# RPiCanInterface.net
KiCad netlist of a schematic drawn in EAGLE
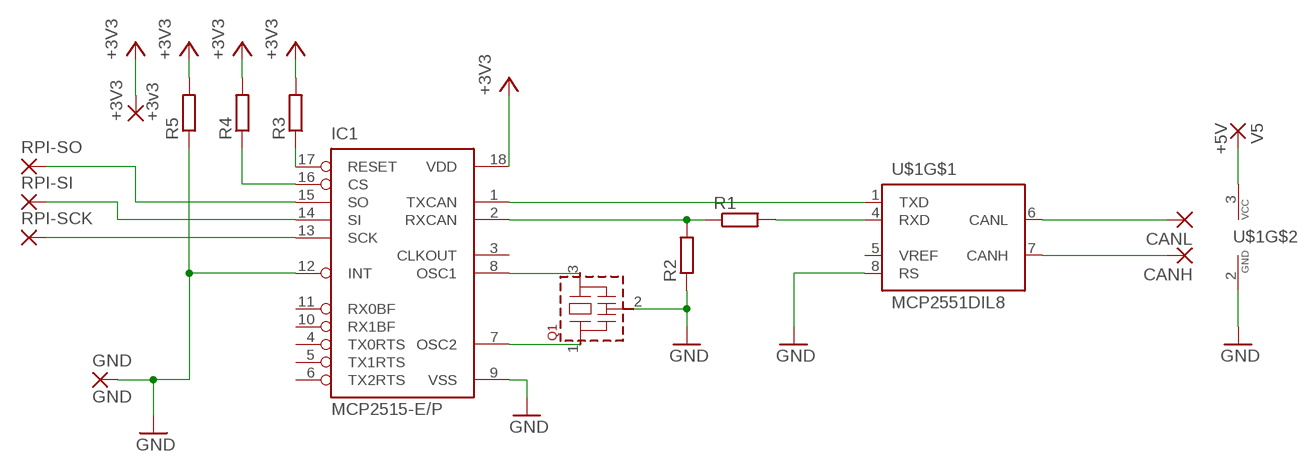
[diagram p0: schematic, sheet 1]

(export (version "E")
  (design (tool "Eeschema 10.0.6"))
  (components
    (comp (ref "+3V3")
      (value "+3v3")
      (footprint "eagle-import:1,6_0,8")
      (libsource (lib "eagle-import") (part "1,6/0,8"))
    )
    (comp (ref "CANH")
      (value "1,6/0,8")
      (footprint "eagle-import:1,6_0,8")
      (libsource (lib "eagle-import") (part "1,6/0,8"))
    )
    (comp (ref "CANL")
      (value "1,6/0,8")
      (footprint "eagle-import:1,6_0,8")
      (libsource (lib "eagle-import") (part "1,6/0,8"))
    )
    (comp (ref "GND")
      (value "GND")
      (footprint "eagle-import:1,6_0,8")
      (libsource (lib "eagle-import") (part "1,6/0,8"))
    )
    (comp (ref "IC1")
      (value "MCP2515-E/P")
      (footprint "eagle-import:DIL18")
      (libsource (lib "eagle-import") (part "MCP2515-E/P"))
    )
    (comp (ref "Q1")
      (value "CSTLA_T")
      (footprint "eagle-import:CSTLA_T")
      (libsource (lib "eagle-import") (part "CSTLA_T"))
    )
    (comp (ref "R1")
      (value "R-EU_0207/7")
      (footprint "eagle-import:0207_7")
      (libsource (lib "eagle-import") (part "R-EU_0207/7"))
    )
    (comp (ref "R2")
      (value "R-EU_0207/7")
      (footprint "eagle-import:0207_7")
      (libsource (lib "eagle-import") (part "R-EU_0207/7"))
    )
    (comp (ref "R3")
      (value "R-EU_0207/7")
      (footprint "eagle-import:0207_7")
      (libsource (lib "eagle-import") (part "R-EU_0207/7"))
    )
    (comp (ref "R4")
      (value "R-EU_0207/7")
      (footprint "eagle-import:0207_7")
      (libsource (lib "eagle-import") (part "R-EU_0207/7"))
    )
    (comp (ref "R5")
      (value "R-EU_0207/7")
      (footprint "eagle-import:0207_7")
      (libsource (lib "eagle-import") (part "R-EU_0207/7"))
    )
    (comp (ref "RPI-SCK")
      (value "1,6/0,8")
      (footprint "eagle-import:1,6_0,8")
      (libsource (lib "eagle-import") (part "1,6/0,8"))
    )
    (comp (ref "RPI-SI")
      (value "1,6/0,8")
      (footprint "eagle-import:1,6_0,8")
      (libsource (lib "eagle-import") (part "1,6/0,8"))
    )
    (comp (ref "RPI-SO")
      (value "1,6/0,8")
      (footprint "eagle-import:1,6_0,8")
      (libsource (lib "eagle-import") (part "1,6/0,8"))
    )
    (comp (ref "U$1")
      (value "MCP2551DIL8")
      (footprint "eagle-import:DIL08")
      (libsource (lib "eagle-import") (part "MCP2551DIL8"))
    )
    (comp (ref "V5")
      (value "+5V")
      (footprint "eagle-import:1,6_0,8")
      (libsource (lib "eagle-import") (part "1,6/0,8"))
    )
  )
  (nets
    (net (code "1") (name "+3V3") (class "Default")
      (node (ref "+3V3") (pin "1") (pinfunction "P_1") (pintype "passive"))
      (node (ref "IC1") (pin "18") (pinfunction "VDD_18") (pintype "power_in"))
      (node (ref "R3") (pin "2") (pinfunction "2_2") (pintype "passive"))
      (node (ref "R4") (pin "2") (pinfunction "2_2") (pintype "passive"))
      (node (ref "R5") (pin "2") (pinfunction "2_2") (pintype "passive"))
    )
    (net (code "2") (name "GND") (class "Default")
      (node (ref "GND") (pin "1") (pinfunction "P_1") (pintype "passive"))
      (node (ref "IC1") (pin "12") (pinfunction "INT_12") (pintype "output"))
      (node (ref "IC1") (pin "9") (pinfunction "VSS_9") (pintype "power_in"))
      (node (ref "Q1") (pin "2") (pinfunction "VSS_2") (pintype "power_in"))
      (node (ref "R2") (pin "1") (pinfunction "1_1") (pintype "passive"))
      (node (ref "R5") (pin "1") (pinfunction "1_1") (pintype "passive"))
      (node (ref "U$1") (pin "2") (pinfunction "GND_2") (pintype "power_in"))
      (node (ref "U$1") (pin "8") (pinfunction "RS_8") (pintype "bidirectional"))
    )
    (net (code "3") (name "Net-(CANH-P)") (class "Default")
      (node (ref "CANH") (pin "1") (pinfunction "P_1") (pintype "passive"))
      (node (ref "U$1") (pin "7") (pinfunction "CANH_7") (pintype "bidirectional"))
    )
    (net (code "4") (name "Net-(CANL-P)") (class "Default")
      (node (ref "CANL") (pin "1") (pinfunction "P_1") (pintype "passive"))
      (node (ref "U$1") (pin "6") (pinfunction "CANL_6") (pintype "bidirectional"))
    )
    (net (code "5") (name "Net-(IC1-CS)") (class "Default")
      (node (ref "IC1") (pin "16") (pinfunction "CS_16") (pintype "input"))
      (node (ref "R4") (pin "1") (pinfunction "1_1") (pintype "passive"))
    )
    (net (code "6") (name "Net-(IC1-OSC1)") (class "Default")
      (node (ref "IC1") (pin "8") (pinfunction "OSC1_8") (pintype "input"))
      (node (ref "Q1") (pin "3") (pinfunction "3_3") (pintype "input"))
    )
    (net (code "7") (name "Net-(IC1-OSC2)") (class "Default")
      (node (ref "IC1") (pin "7") (pinfunction "OSC2_7") (pintype "output"))
      (node (ref "Q1") (pin "1") (pinfunction "1_1") (pintype "output"))
    )
    (net (code "8") (name "Net-(IC1-RESET)") (class "Default")
      (node (ref "IC1") (pin "17") (pinfunction "RESET_17") (pintype "input"))
      (node (ref "R3") (pin "1") (pinfunction "1_1") (pintype "passive"))
    )
    (net (code "9") (name "Net-(IC1-RXCAN)") (class "Default")
      (node (ref "IC1") (pin "2") (pinfunction "RXCAN_2") (pintype "input"))
      (node (ref "R1") (pin "1") (pinfunction "1_1") (pintype "passive"))
      (node (ref "R2") (pin "2") (pinfunction "2_2") (pintype "passive"))
    )
    (net (code "10") (name "Net-(IC1-SCK)") (class "Default")
      (node (ref "IC1") (pin "13") (pinfunction "SCK_13") (pintype "input"))
      (node (ref "RPI-SCK") (pin "1") (pinfunction "P_1") (pintype "passive"))
    )
    (net (code "11") (name "Net-(IC1-SI)") (class "Default")
      (node (ref "IC1") (pin "14") (pinfunction "SI_14") (pintype "input"))
      (node (ref "RPI-SI") (pin "1") (pinfunction "P_1") (pintype "passive"))
    )
    (net (code "12") (name "Net-(IC1-SO)") (class "Default")
      (node (ref "IC1") (pin "15") (pinfunction "SO_15") (pintype "output"))
      (node (ref "RPI-SO") (pin "1") (pinfunction "P_1") (pintype "passive"))
    )
    (net (code "13") (name "Net-(IC1-TXCAN)") (class "Default")
      (node (ref "IC1") (pin "1") (pinfunction "TXCAN_1") (pintype "output"))
      (node (ref "U$1") (pin "1") (pinfunction "TXD_1") (pintype "bidirectional"))
    )
    (net (code "14") (name "Net-(U$1A-RXD)") (class "Default")
      (node (ref "R1") (pin "2") (pinfunction "2_2") (pintype "passive"))
      (node (ref "U$1") (pin "4") (pinfunction "RXD_4") (pintype "bidirectional"))
    )
    (net (code "15") (name "Net-(U$1B-VCC)") (class "Default")
      (node (ref "U$1") (pin "3") (pinfunction "VCC_3") (pintype "power_in"))
      (node (ref "V5") (pin "1") (pinfunction "P_1") (pintype "passive"))
    )
    (net (code "16") (name "unconnected-(IC1-CLKOUT-Pad3)") (class "Default")
      (node (ref "IC1") (pin "3") (pinfunction "CLKOUT_3") (pintype "output"))
    )
    (net (code "17") (name "unconnected-(IC1-RX0BF-Pad11)") (class "Default")
      (node (ref "IC1") (pin "11") (pinfunction "RX0BF_11") (pintype "output"))
    )
    (net (code "18") (name "unconnected-(IC1-RX1BF-Pad10)") (class "Default")
      (node (ref "IC1") (pin "10") (pinfunction "RX1BF_10") (pintype "output"))
    )
    (net (code "19") (name "unconnected-(IC1-TX0RTS-Pad4)") (class "Default")
      (node (ref "IC1") (pin "4") (pinfunction "TX0RTS_4") (pintype "input"))
    )
    (net (code "20") (name "unconnected-(IC1-TX1RTS-Pad5)") (class "Default")
      (node (ref "IC1") (pin "5") (pinfunction "TX1RTS_5") (pintype "input"))
    )
    (net (code "21") (name "unconnected-(IC1-TX2RTS-Pad6)") (class "Default")
      (node (ref "IC1") (pin "6") (pinfunction "TX2RTS_6") (pintype "input"))
    )
    (net (code "22") (name "unconnected-(U$1A-VREF-Pad5)") (class "Default")
      (node (ref "U$1") (pin "5") (pinfunction "VREF_5") (pintype "bidirectional"))
    )
  )
)
